# amc7135-testboard-mk-1_1.net
KiCad netlist of a schematic drawn in EAGLE
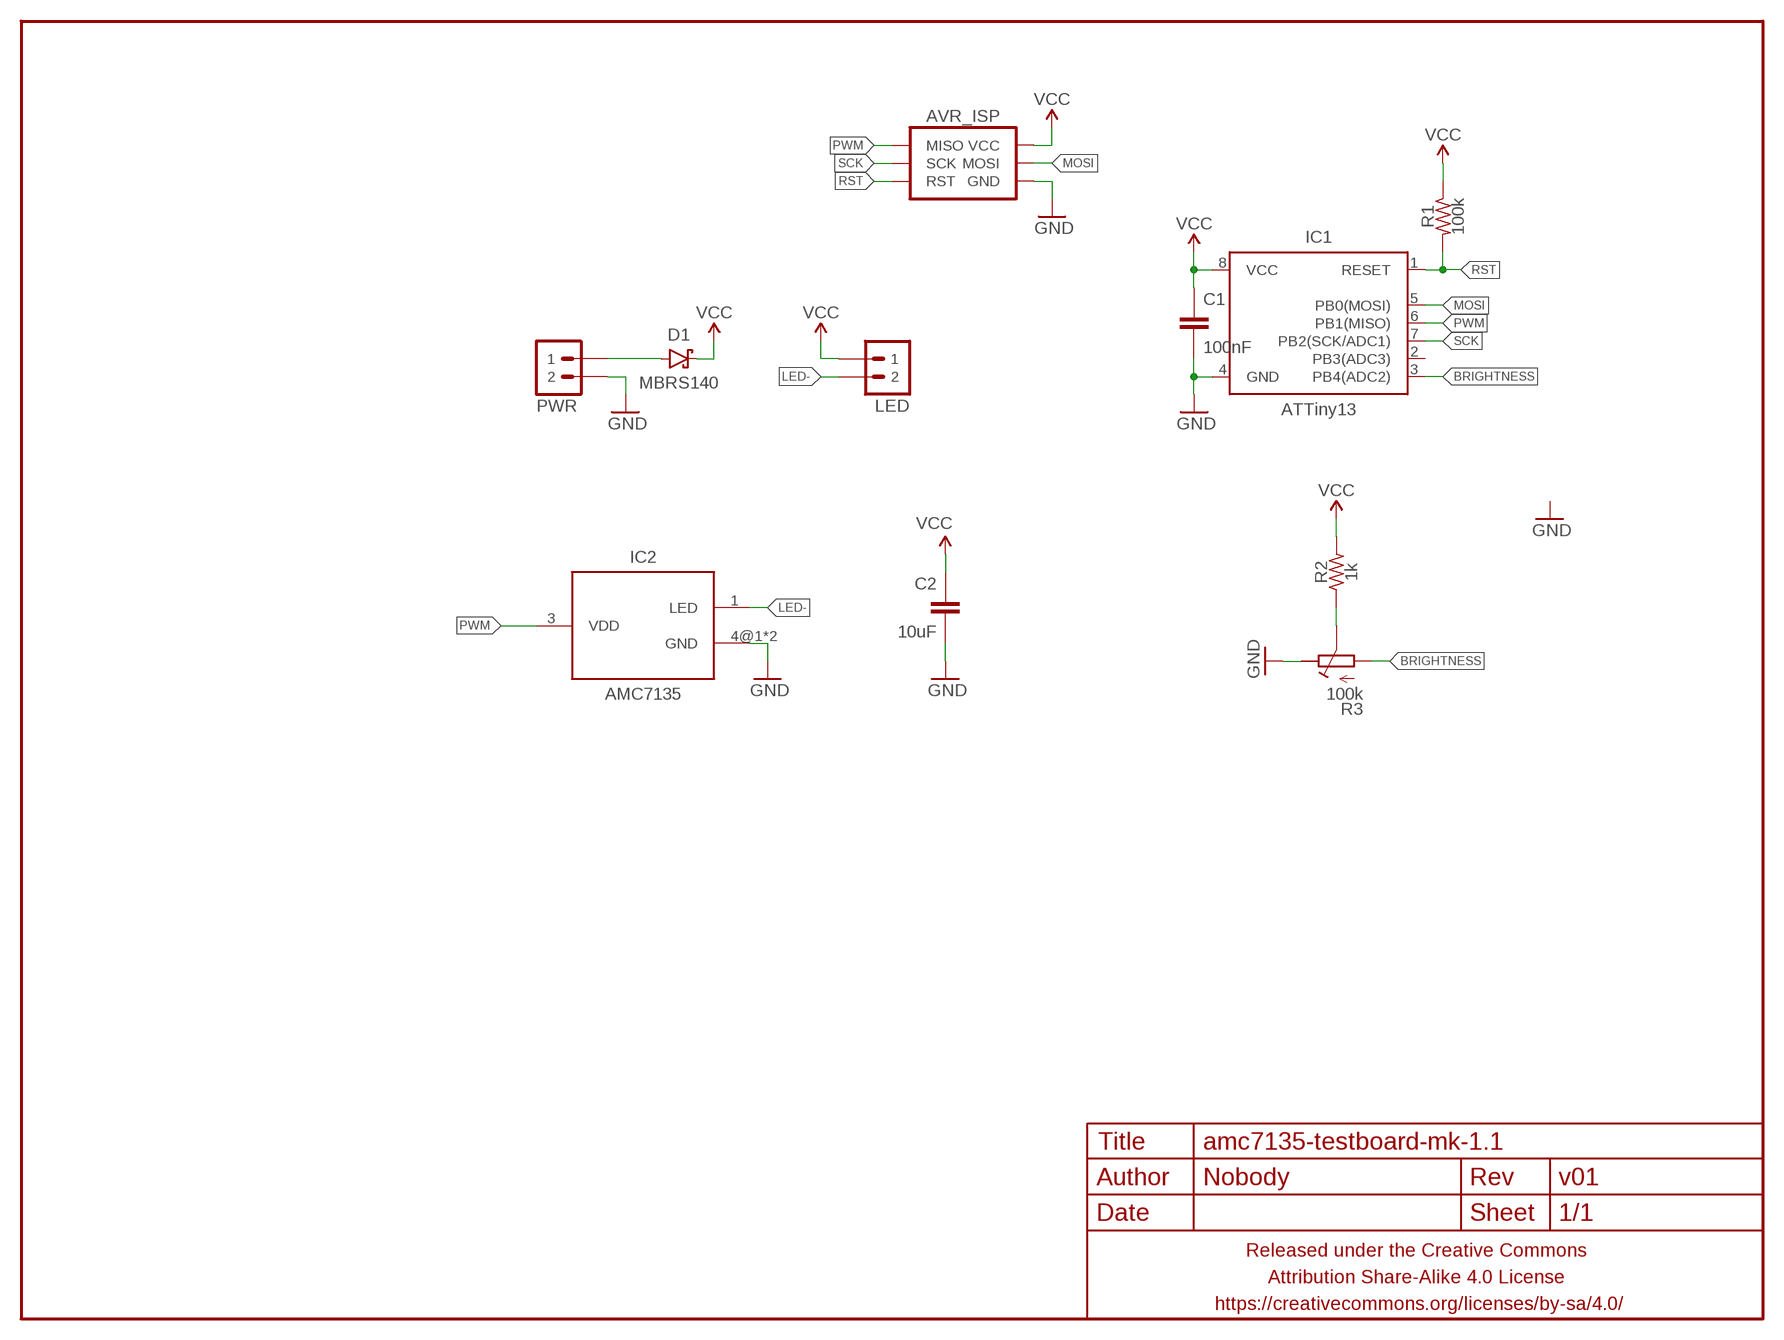
[diagram p0: schematic, sheet 1]

(export (version "E")
  (design (tool "Eeschema 10.0.6"))
  (components
    (comp (ref "AVR_ISP")
      (value "AVR_SPI_PRG_6SMD_TEST_POINTS")
      (footprint "eagle-import:2X3_SMD_TEST_POINTS")
      (libsource (lib "eagle-import") (part "AVR_SPI_PRG_6SMD_TEST_POINTS"))
    )
    (comp (ref "C1")
      (value "100nF")
      (footprint "eagle-import:C0603-TIGHTER")
      (libsource (lib "eagle-import") (part "CAPACITOR-CERAMICC0603-TIGHTER"))
    )
    (comp (ref "C2")
      (value "10uF")
      (footprint "eagle-import:C1210")
      (libsource (lib "eagle-import") (part "CAPACITOR-CERAMICC1210"))
    )
    (comp (ref "D1")
      (value "MBRS140")
      (footprint "eagle-import:SOD123-SCHOTTKY")
      (libsource (lib "eagle-import") (part "DIODE-SCHOTTKYSOD123"))
    )
    (comp (ref "FRAME1")
      (value "FRAME-LETTERNO_PACKAGE")
      (footprint "eagle-import:DUMMY")
      (fields (field (name "DESIGNER") "Nobody"))
      (libsource (lib "eagle-import") (part "FRAME-LETTERNO_PACKAGE"))
    )
    (comp (ref "IC1")
      (value "ATTiny13")
      (footprint "eagle-import:SO08")
      (libsource (lib "eagle-import") (part "ATTINY13SOIC"))
    )
    (comp (ref "IC2")
      (value "AMC7135")
      (footprint "eagle-import:SOT89-NOTHERM")
      (libsource (lib "eagle-import") (part "AMC7135SOT-89-NOTHERM"))
    )
    (comp (ref "LED")
      (value "M02PTH-CENTERED")
      (footprint "eagle-import:1X02-CENTER")
      (libsource (lib "eagle-import") (part "M02PTH-CENTERED"))
    )
    (comp (ref "PWR")
      (value "M02PTH-CENTERED")
      (footprint "eagle-import:1X02-CENTER")
      (libsource (lib "eagle-import") (part "M02PTH-CENTERED"))
    )
    (comp (ref "R1")
      (value "100k")
      (footprint "eagle-import:R0603-TIGHTER")
      (libsource (lib "eagle-import") (part "RESISTORR0603-TIGHTER"))
    )
    (comp (ref "R2")
      (value "1k")
      (footprint "eagle-import:R0603-TIGHTER")
      (libsource (lib "eagle-import") (part "RESISTORR0603-TIGHTER"))
    )
    (comp (ref "R3")
      (value "100k")
      (footprint "eagle-import:EVM3Y")
      (libsource (lib "eagle-import") (part "POTENTIOMETEREVM3Y"))
    )
  )
  (nets
    (net (code "1") (name "BRIGHTNESS") (class "Default")
      (node (ref "IC1") (pin "3") (pinfunction "PB4(ADC2)_3") (pintype "bidirectional"))
      (node (ref "R3") (pin "A") (pinfunction "A_A") (pintype "passive"))
    )
    (net (code "2") (name "GND") (class "Default")
      (node (ref "AVR_ISP") (pin "6") (pinfunction "GND_6") (pintype "passive"))
      (node (ref "C1") (pin "2") (pinfunction "2_2") (pintype "passive"))
      (node (ref "C2") (pin "2") (pinfunction "2_2") (pintype "passive"))
      (node (ref "IC1") (pin "4") (pinfunction "GND_4") (pintype "bidirectional"))
      (node (ref "IC2") (pin "4@1") (pinfunction "GND_4@1") (pintype "bidirectional"))
      (node (ref "IC2") (pin "4@2") (pinfunction "GND_4@2") (pintype "bidirectional"))
      (node (ref "PWR") (pin "2") (pinfunction "2_2") (pintype "passive"))
      (node (ref "R3") (pin "E") (pinfunction "E_E") (pintype "passive"))
    )
    (net (code "3") (name "LED-") (class "Default")
      (node (ref "IC2") (pin "1") (pinfunction "LED_1") (pintype "bidirectional"))
      (node (ref "LED") (pin "2") (pinfunction "2_2") (pintype "passive"))
    )
    (net (code "4") (name "MOSI") (class "Default")
      (node (ref "AVR_ISP") (pin "4") (pinfunction "MOSI_4") (pintype "passive"))
      (node (ref "IC1") (pin "5") (pinfunction "PB0(MOSI)_5") (pintype "bidirectional"))
    )
    (net (code "5") (name "Net-(D1-PadA)") (class "Default")
      (node (ref "D1") (pin "A") (pinfunction "A_A") (pintype "passive"))
      (node (ref "PWR") (pin "1") (pinfunction "1_1") (pintype "passive"))
    )
    (net (code "6") (name "Net-(R2-Pad1)") (class "Default")
      (node (ref "R2") (pin "1") (pinfunction "1_1") (pintype "passive"))
      (node (ref "R3") (pin "S") (pinfunction "S_S") (pintype "passive"))
    )
    (net (code "7") (name "PWM") (class "Default")
      (node (ref "AVR_ISP") (pin "1") (pinfunction "MISO_1") (pintype "passive"))
      (node (ref "IC1") (pin "6") (pinfunction "PB1(MISO)_6") (pintype "bidirectional"))
      (node (ref "IC2") (pin "3") (pinfunction "VDD_3") (pintype "bidirectional"))
    )
    (net (code "8") (name "RST") (class "Default")
      (node (ref "AVR_ISP") (pin "5") (pinfunction "RST_5") (pintype "passive"))
      (node (ref "IC1") (pin "1") (pinfunction "RESET_1") (pintype "bidirectional"))
      (node (ref "R1") (pin "2") (pinfunction "2_2") (pintype "passive"))
    )
    (net (code "9") (name "SCK") (class "Default")
      (node (ref "AVR_ISP") (pin "3") (pinfunction "SCK_3") (pintype "passive"))
      (node (ref "IC1") (pin "7") (pinfunction "PB2(SCK/ADC1)_7") (pintype "bidirectional"))
    )
    (net (code "10") (name "VCC") (class "Default")
      (node (ref "AVR_ISP") (pin "2") (pinfunction "VCC_2") (pintype "passive"))
      (node (ref "C1") (pin "1") (pinfunction "1_1") (pintype "passive"))
      (node (ref "C2") (pin "1") (pinfunction "1_1") (pintype "passive"))
      (node (ref "D1") (pin "C") (pinfunction "C_C") (pintype "passive"))
      (node (ref "IC1") (pin "8") (pinfunction "VCC_8") (pintype "bidirectional"))
      (node (ref "LED") (pin "1") (pinfunction "1_1") (pintype "passive"))
      (node (ref "R1") (pin "1") (pinfunction "1_1") (pintype "passive"))
      (node (ref "R2") (pin "2") (pinfunction "2_2") (pintype "passive"))
    )
    (net (code "11") (name "unconnected-(IC1-PB3(ADC3)-Pad2)") (class "Default")
      (node (ref "IC1") (pin "2") (pinfunction "PB3(ADC3)_2") (pintype "bidirectional"))
    )
  )
)
